# ManitoBoardLP1.net
KiCad netlist of a schematic drawn in EAGLE
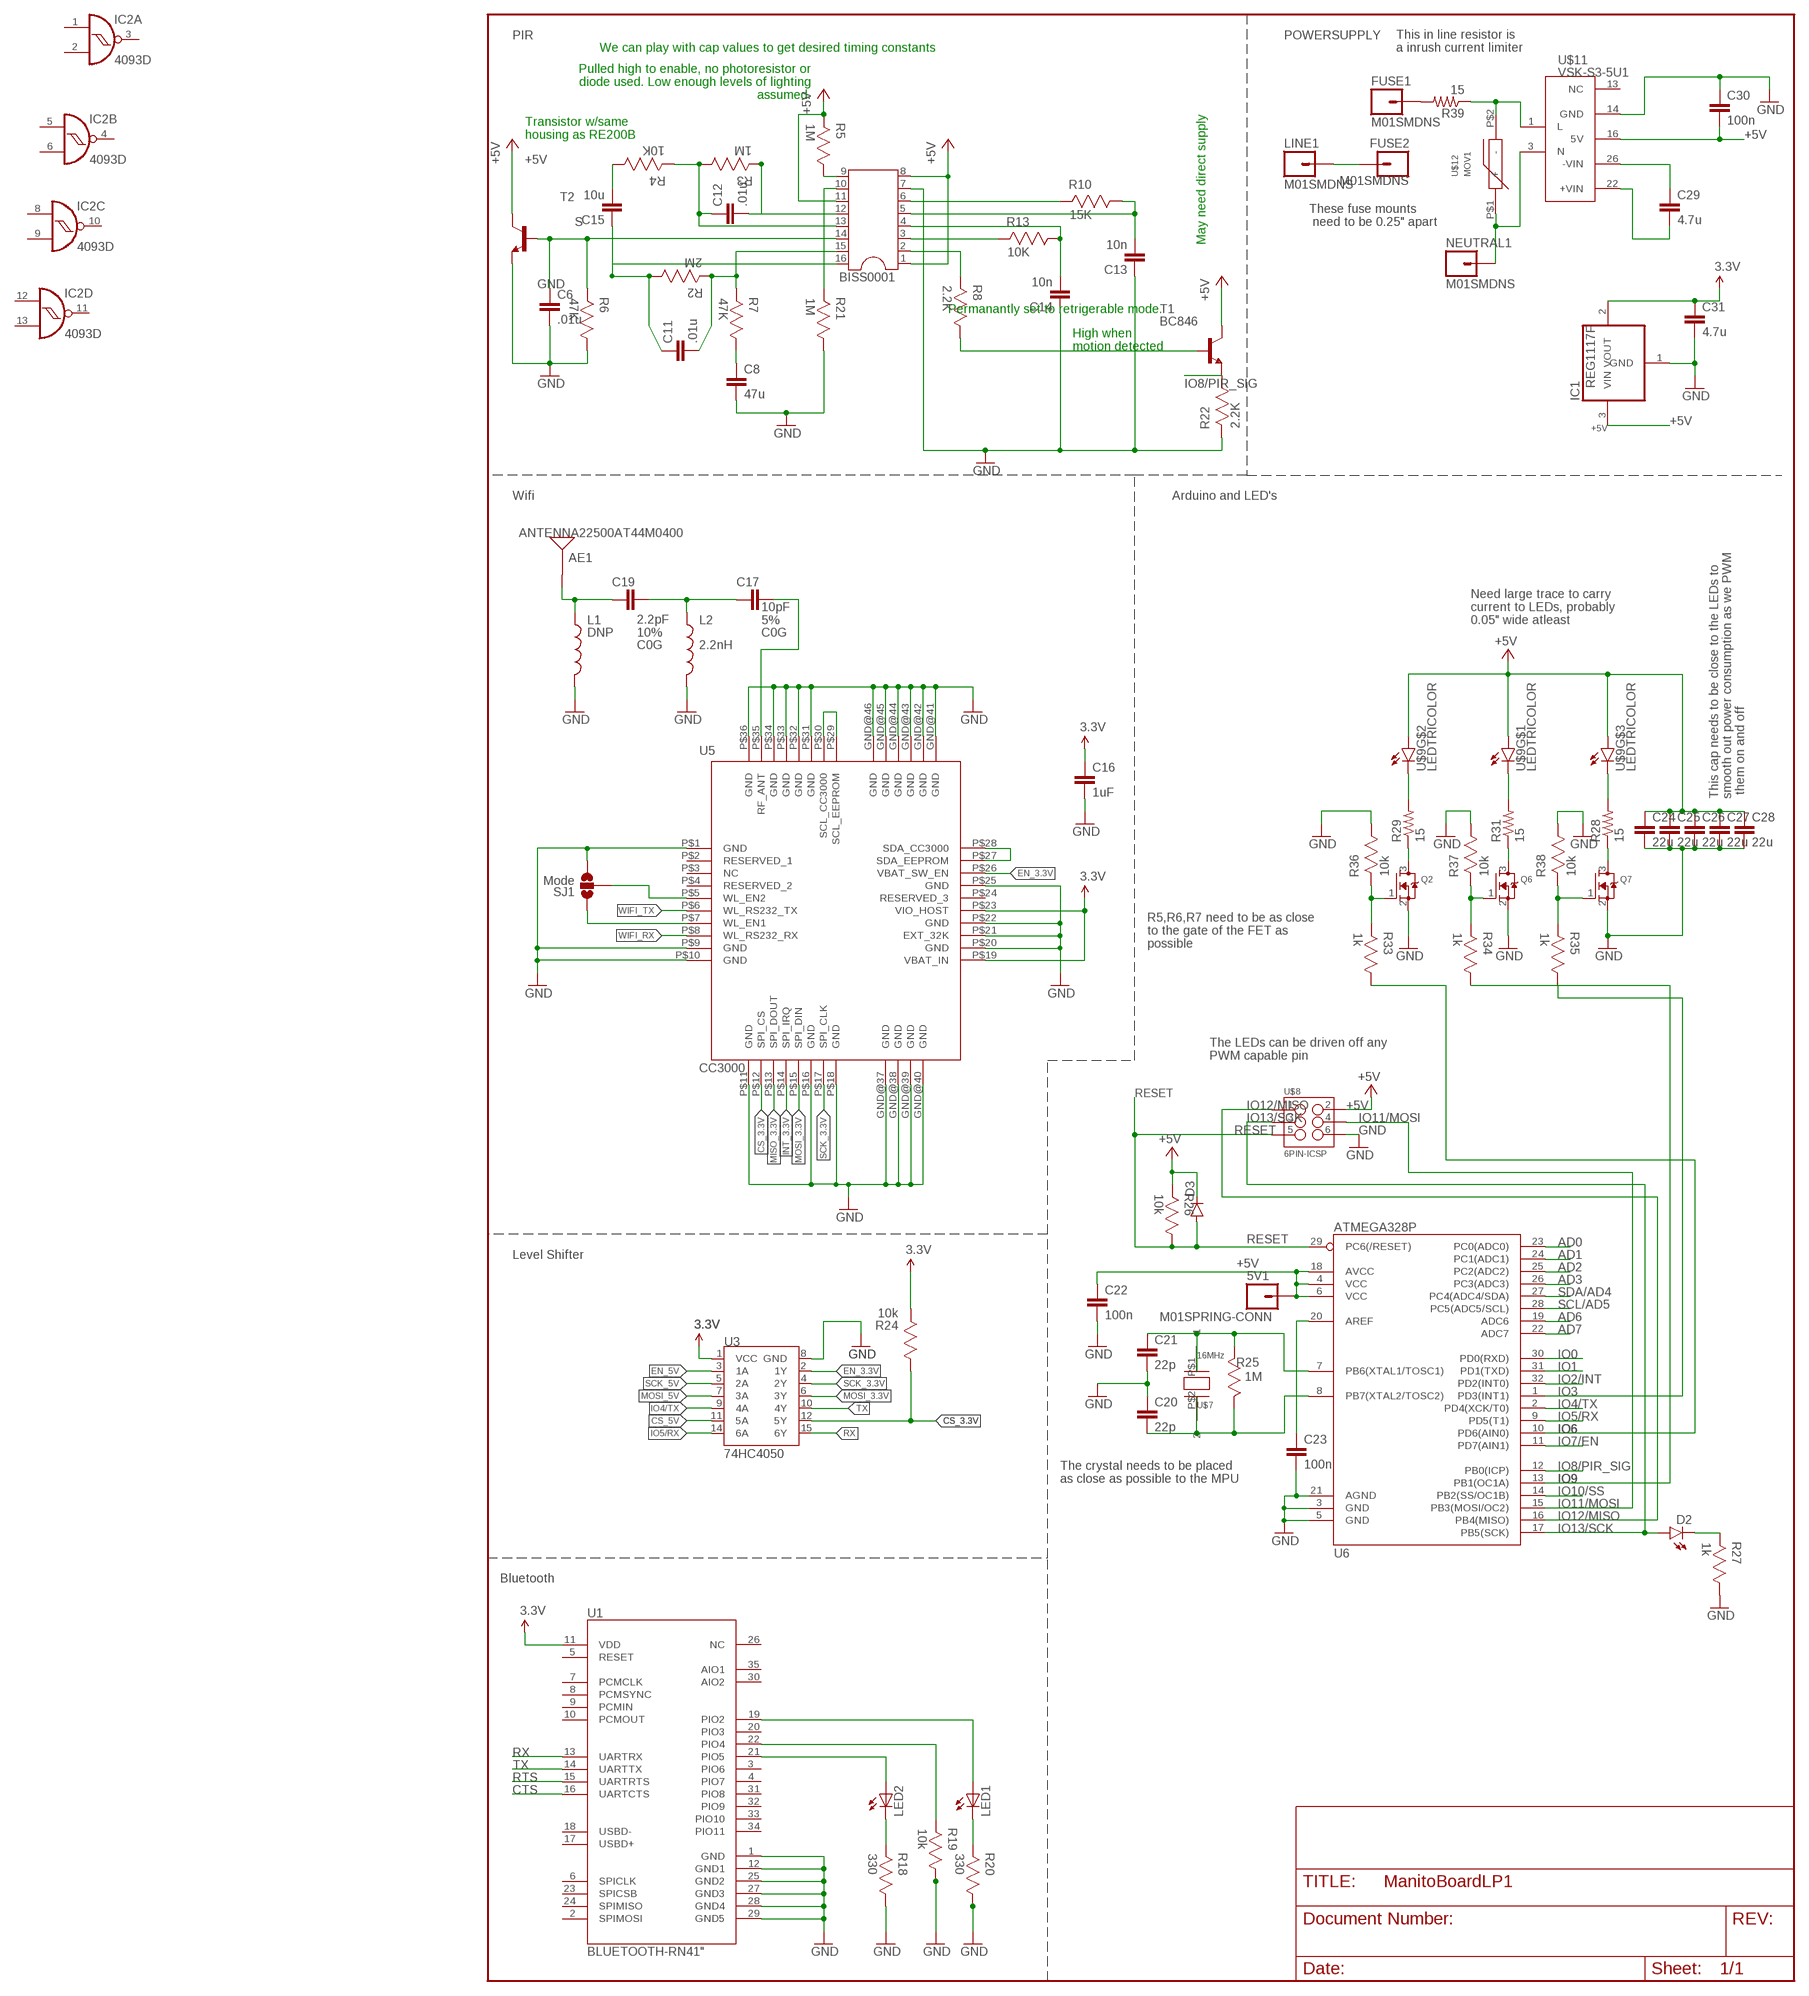
[diagram p0: schematic, sheet 1]

(export (version "E")
  (design (tool "Eeschema 10.0.6"))
  (components
    (comp (ref "5V1")
      (value "M01SPRING-CONN")
      (footprint "eagle-import:SPRING-CONNECTOR")
      (libsource (lib "eagle-import") (part "M01SPRING-CONN"))
    )
    (comp (ref "AE1")
      (value "ANTENNA22500AT44M0400")
      (footprint "eagle-import:ANTENNA-CHIP_2500AT44M0400")
      (libsource (lib "eagle-import") (part "ANTENNA22500AT44M0400"))
    )
    (comp (ref "BISS0001")
      (value "DIL16S")
      (footprint "eagle-import:SOCKET-16")
      (libsource (lib "eagle-import") (part "DIL16S"))
    )
    (comp (ref "C6")
      (value ".01u")
      (footprint "eagle-import:0805")
      (libsource (lib "eagle-import") (part "CAP0805"))
    )
    (comp (ref "C8")
      (value "47u")
      (footprint "eagle-import:0805")
      (libsource (lib "eagle-import") (part "CAP0805"))
    )
    (comp (ref "C11")
      (value ".01u")
      (footprint "eagle-import:0805")
      (libsource (lib "eagle-import") (part "CAP0805"))
    )
    (comp (ref "C12")
      (value ".01u")
      (footprint "eagle-import:0805")
      (libsource (lib "eagle-import") (part "CAP0805"))
    )
    (comp (ref "C13")
      (value "10n")
      (footprint "eagle-import:0805")
      (libsource (lib "eagle-import") (part "CAP0805"))
    )
    (comp (ref "C14")
      (value "10n")
      (footprint "eagle-import:0805")
      (libsource (lib "eagle-import") (part "CAP0805"))
    )
    (comp (ref "C15")
      (value "10u")
      (footprint "eagle-import:0805")
      (libsource (lib "eagle-import") (part "CAP0805"))
    )
    (comp (ref "C16")
      (value "1uF")
      (footprint "eagle-import:0805")
      (libsource (lib "eagle-import") (part "SparkFun-Capacitors_CAP0805"))
    )
    (comp (ref "C17")
      (value "10pF")
      (footprint "eagle-import:0603-CAP")
      (fields (field (name "COEFF") "C0G") (field (name "TOL") "5%"))
      (libsource (lib "eagle-import") (part "SparkFun-Capacitors_CAP0603-CAP"))
    )
    (comp (ref "C19")
      (value "2.2pF")
      (footprint "eagle-import:0603-CAP")
      (fields (field (name "COEFF") "C0G") (field (name "TOL") "10%"))
      (libsource (lib "eagle-import") (part "SparkFun-Capacitors_CAP0603-CAP"))
    )
    (comp (ref "C20")
      (value "22p")
      (footprint "eagle-import:0603-CAP")
      (libsource (lib "eagle-import") (part "CAP0603-CAP"))
    )
    (comp (ref "C21")
      (value "22p")
      (footprint "eagle-import:0603-CAP")
      (libsource (lib "eagle-import") (part "CAP0603-CAP"))
    )
    (comp (ref "C22")
      (value "100n")
      (footprint "eagle-import:0603-CAP")
      (libsource (lib "eagle-import") (part "CAP0603-CAP"))
    )
    (comp (ref "C23")
      (value "100n")
      (footprint "eagle-import:0603-CAP")
      (libsource (lib "eagle-import") (part "CAP0603-CAP"))
    )
    (comp (ref "C24")
      (value "22u")
      (footprint "eagle-import:0603-CAP")
      (libsource (lib "eagle-import") (part "CAP0603-CAP"))
    )
    (comp (ref "C25")
      (value "22u")
      (footprint "eagle-import:0603-CAP")
      (libsource (lib "eagle-import") (part "CAP0603-CAP"))
    )
    (comp (ref "C26")
      (value "22u")
      (footprint "eagle-import:0603-CAP")
      (libsource (lib "eagle-import") (part "CAP0603-CAP"))
    )
    (comp (ref "C27")
      (value "22u")
      (footprint "eagle-import:0603-CAP")
      (libsource (lib "eagle-import") (part "CAP0603-CAP"))
    )
    (comp (ref "C28")
      (value "22u")
      (footprint "eagle-import:0603-CAP")
      (libsource (lib "eagle-import") (part "CAP0603-CAP"))
    )
    (comp (ref "C29")
      (value "4.7u")
      (footprint "eagle-import:0603-CAP")
      (libsource (lib "eagle-import") (part "CAP0603-CAP"))
    )
    (comp (ref "C30")
      (value "100n")
      (footprint "eagle-import:0603-CAP")
      (libsource (lib "eagle-import") (part "CAP0603-CAP"))
    )
    (comp (ref "C31")
      (value "4.7u")
      (footprint "eagle-import:0603-CAP")
      (libsource (lib "eagle-import") (part "CAP0603-CAP"))
    )
    (comp (ref "D2")
      (value "LED-YELLOW0603")
      (footprint "eagle-import:LED-0603")
      (libsource (lib "eagle-import") (part "LED-YELLOW0603"))
    )
    (comp (ref "D3")
      (value "DIODE1N4148")
      (footprint "eagle-import:DIODE-1N4148")
      (libsource (lib "eagle-import") (part "DIODE1N4148"))
    )
    (comp (ref "FUSE1")
      (value "M01SMDNS")
      (footprint "eagle-import:1X01NS")
      (libsource (lib "eagle-import") (part "M01SMDNS"))
    )
    (comp (ref "FUSE2")
      (value "M01SMDNS")
      (footprint "eagle-import:1X01NS")
      (libsource (lib "eagle-import") (part "M01SMDNS"))
    )
    (comp (ref "IC1")
      (value "REG1117F")
      (footprint "eagle-import:DD-3")
      (fields (field (name "MF") "TEXAS INSTRUMENTS") (field (name "MPN") "REG1117FAKTTT"))
      (libsource (lib "eagle-import") (part "REG1117F"))
    )
    (comp (ref "IC2")
      (value "4093D")
      (footprint "eagle-import:SO14")
      (libsource (lib "eagle-import") (part "4093D"))
    )
    (comp (ref "L1")
      (value "DNP")
      (footprint "eagle-import:0603")
      (libsource (lib "eagle-import") (part "INDUCTOR0603"))
    )
    (comp (ref "L2")
      (value "2.2nH")
      (footprint "eagle-import:0603")
      (libsource (lib "eagle-import") (part "INDUCTOR0603"))
    )
    (comp (ref "LED1")
      (value "LED_ESML0603")
      (footprint "eagle-import:LED_SML0603")
      (libsource (lib "eagle-import") (part "LED_ESML0603"))
    )
    (comp (ref "LED2")
      (value "LED_ESML0603")
      (footprint "eagle-import:LED_SML0603")
      (libsource (lib "eagle-import") (part "LED_ESML0603"))
    )
    (comp (ref "LINE1")
      (value "M01SMDNS")
      (footprint "eagle-import:1X01NS")
      (libsource (lib "eagle-import") (part "M01SMDNS"))
    )
    (comp (ref "NEUTRAL1")
      (value "M01SMDNS")
      (footprint "eagle-import:1X01NS")
      (libsource (lib "eagle-import") (part "M01SMDNS"))
    )
    (comp (ref "Q2")
      (value "MOSFET-NREFLOW")
      (footprint "eagle-import:SOT23")
      (libsource (lib "eagle-import") (part "MOSFET-NREFLOW"))
    )
    (comp (ref "Q6")
      (value "MOSFET-NREFLOW")
      (footprint "eagle-import:SOT23")
      (libsource (lib "eagle-import") (part "MOSFET-NREFLOW"))
    )
    (comp (ref "Q7")
      (value "MOSFET-NREFLOW")
      (footprint "eagle-import:SOT23")
      (libsource (lib "eagle-import") (part "MOSFET-NREFLOW"))
    )
    (comp (ref "R2")
      (value "2M")
      (footprint "eagle-import:0603RESISTOR")
      (fields (field (name "MPN") "CRCW06031K21FKEA") (field (name "TOLERANCE") "± 1.0 %"))
      (libsource (lib "eagle-import") (part "0603RESISTOR1"))
    )
    (comp (ref "R3")
      (value "1M")
      (footprint "eagle-import:0603RESISTOR")
      (fields (field (name "MPN") "CRCW06031K21FKEA") (field (name "TOLERANCE") "± 1.0 %"))
      (libsource (lib "eagle-import") (part "0603RESISTOR1"))
    )
    (comp (ref "R4")
      (value "10K")
      (footprint "eagle-import:0603RESISTOR")
      (fields (field (name "MPN") "CRCW06031K21FKEA") (field (name "TOLERANCE") "± 1.0 %"))
      (libsource (lib "eagle-import") (part "0603RESISTOR1"))
    )
    (comp (ref "R5")
      (value "1M")
      (footprint "eagle-import:0603RESISTOR")
      (fields (field (name "MPN") "CRCW06031K21FKEA") (field (name "TOLERANCE") "± 1.0 %"))
      (libsource (lib "eagle-import") (part "0603RESISTOR1"))
    )
    (comp (ref "R6")
      (value "47K")
      (footprint "eagle-import:0603RESISTOR")
      (fields (field (name "MPN") "CRCW06031K21FKEA") (field (name "TOLERANCE") "± 1.0 %"))
      (libsource (lib "eagle-import") (part "0603RESISTOR1"))
    )
    (comp (ref "R7")
      (value "47K")
      (footprint "eagle-import:0603RESISTOR")
      (fields (field (name "MPN") "CRCW06031K21FKEA") (field (name "TOLERANCE") "± 1.0 %"))
      (libsource (lib "eagle-import") (part "0603RESISTOR1"))
    )
    (comp (ref "R8")
      (value "2.2K")
      (footprint "eagle-import:0603RESISTOR")
      (fields (field (name "MPN") "CRCW06031K21FKEA") (field (name "TOLERANCE") "± 1.0 %"))
      (libsource (lib "eagle-import") (part "0603RESISTOR1"))
    )
    (comp (ref "R10")
      (value "15K")
      (footprint "eagle-import:0603RESISTOR")
      (fields (field (name "MPN") "CRCW06031K21FKEA") (field (name "TOLERANCE") "± 1.0 %"))
      (libsource (lib "eagle-import") (part "0603RESISTOR1"))
    )
    (comp (ref "R13")
      (value "10K")
      (footprint "eagle-import:0603RESISTOR")
      (fields (field (name "MPN") "CRCW06031K21FKEA") (field (name "TOLERANCE") "± 1.0 %"))
      (libsource (lib "eagle-import") (part "0603RESISTOR1"))
    )
    (comp (ref "R18")
      (value "330")
      (footprint "eagle-import:0603RESISTOR")
      (fields (field (name "MPN") "CRCW06031K21FKEA") (field (name "TOLERANCE") "± 1.0 %"))
      (libsource (lib "eagle-import") (part "0603RESISTOR1"))
    )
    (comp (ref "R19")
      (value "10k")
      (footprint "eagle-import:0603RESISTOR")
      (fields (field (name "MPN") "CRCW06031K21FKEA") (field (name "TOLERANCE") "± 1.0 %"))
      (libsource (lib "eagle-import") (part "0603RESISTOR1"))
    )
    (comp (ref "R20")
      (value "330")
      (footprint "eagle-import:0603RESISTOR")
      (fields (field (name "MPN") "CRCW06031K21FKEA") (field (name "TOLERANCE") "± 1.0 %"))
      (libsource (lib "eagle-import") (part "0603RESISTOR1"))
    )
    (comp (ref "R21")
      (value "1M")
      (footprint "eagle-import:0603RESISTOR")
      (fields (field (name "MPN") "CRCW06031K21FKEA") (field (name "TOLERANCE") "± 1.0 %"))
      (libsource (lib "eagle-import") (part "0603RESISTOR1"))
    )
    (comp (ref "R22")
      (value "2.2K")
      (footprint "eagle-import:0603RESISTOR")
      (fields (field (name "MPN") "CRCW06031K21FKEA") (field (name "TOLERANCE") "± 1.0 %"))
      (libsource (lib "eagle-import") (part "0603RESISTOR1"))
    )
    (comp (ref "R24")
      (value "10k")
      (footprint "eagle-import:0603RESISTOR")
      (fields (field (name "MPN") "CRCW06031K21FKEA") (field (name "TOLERANCE") "± 1.0 %"))
      (libsource (lib "eagle-import") (part "0603RESISTOR1"))
    )
    (comp (ref "R25")
      (value "1M")
      (footprint "eagle-import:0603RESISTOR")
      (fields (field (name "MPN") "CRCW06031K21FKEA") (field (name "TOLERANCE") "± 1.0 %"))
      (libsource (lib "eagle-import") (part "0603RESISTOR1"))
    )
    (comp (ref "R26")
      (value "10k")
      (footprint "eagle-import:0603RESISTOR")
      (fields (field (name "MPN") "CRCW06031K21FKEA") (field (name "TOLERANCE") "± 1.0 %"))
      (libsource (lib "eagle-import") (part "0603RESISTOR1"))
    )
    (comp (ref "R27")
      (value "1k")
      (footprint "eagle-import:0603RESISTOR")
      (fields (field (name "MPN") "CRCW06031K21FKEA") (field (name "TOLERANCE") "± 1.0 %"))
      (libsource (lib "eagle-import") (part "0603RESISTOR1"))
    )
    (comp (ref "R28")
      (value "15")
      (footprint "eagle-import:AXIAL-0.6")
      (libsource (lib "eagle-import") (part "RESISTORPTH-1W"))
    )
    (comp (ref "R29")
      (value "15")
      (footprint "eagle-import:AXIAL-0.6")
      (libsource (lib "eagle-import") (part "RESISTORPTH-1W"))
    )
    (comp (ref "R31")
      (value "15")
      (footprint "eagle-import:AXIAL-0.6")
      (libsource (lib "eagle-import") (part "RESISTORPTH-1W"))
    )
    (comp (ref "R33")
      (value "1k")
      (footprint "eagle-import:0603RESISTOR")
      (fields (field (name "MPN") "CRCW06031K21FKEA") (field (name "TOLERANCE") "± 1.0 %"))
      (libsource (lib "eagle-import") (part "0603RESISTOR1"))
    )
    (comp (ref "R34")
      (value "1k")
      (footprint "eagle-import:0603RESISTOR")
      (fields (field (name "MPN") "CRCW06031K21FKEA") (field (name "TOLERANCE") "± 1.0 %"))
      (libsource (lib "eagle-import") (part "0603RESISTOR1"))
    )
    (comp (ref "R35")
      (value "1k")
      (footprint "eagle-import:0603RESISTOR")
      (fields (field (name "MPN") "CRCW06031K21FKEA") (field (name "TOLERANCE") "± 1.0 %"))
      (libsource (lib "eagle-import") (part "0603RESISTOR1"))
    )
    (comp (ref "R36")
      (value "10k")
      (footprint "eagle-import:0603RESISTOR")
      (fields (field (name "MPN") "CRCW06031K21FKEA") (field (name "TOLERANCE") "± 1.0 %"))
      (libsource (lib "eagle-import") (part "0603RESISTOR1"))
    )
    (comp (ref "R37")
      (value "10k")
      (footprint "eagle-import:0603RESISTOR")
      (fields (field (name "MPN") "CRCW06031K21FKEA") (field (name "TOLERANCE") "± 1.0 %"))
      (libsource (lib "eagle-import") (part "0603RESISTOR1"))
    )
    (comp (ref "R38")
      (value "10k")
      (footprint "eagle-import:0603RESISTOR")
      (fields (field (name "MPN") "CRCW06031K21FKEA") (field (name "TOLERANCE") "± 1.0 %"))
      (libsource (lib "eagle-import") (part "0603RESISTOR1"))
    )
    (comp (ref "R39")
      (value "15")
      (footprint "eagle-import:AXIAL-0.6")
      (libsource (lib "eagle-import") (part "RESISTORPTH-1W"))
    )
    (comp (ref "SJ1")
      (value "Mode")
      (footprint "eagle-import:SJ_3_PASTE1&2")
      (libsource (lib "eagle-import") (part "SOLDERJUMPER_2WAYPASTE1&2"))
    )
    (comp (ref "T1")
      (value "BC846")
      (footprint "eagle-import:SOT23")
      (libsource (lib "eagle-import") (part "BC846"))
    )
    (comp (ref "T2")
      (value "-NPN-TO5")
      (footprint "eagle-import:TO5")
      (libsource (lib "eagle-import") (part "-NPN-TO5"))
    )
    (comp (ref "U$7")
      (value "16MHz")
      (footprint "eagle-import:SMDCRYSTAL")
      (libsource (lib "eagle-import") (part "SMDCRYSTAL"))
    )
    (comp (ref "U$8")
      (value "6PIN-ICSP")
      (footprint "eagle-import:2X3-ICSP")
      (libsource (lib "eagle-import") (part "6PIN-ICSP"))
    )
    (comp (ref "U$9")
      (value "LEDTRICOLOR")
      (footprint "eagle-import:TRICOLORLED")
      (libsource (lib "eagle-import") (part "LEDTRICOLOR"))
    )
    (comp (ref "U$11")
      (value "VSK-S3-5U1")
      (footprint "eagle-import:VSK-S3-DCAC")
      (libsource (lib "eagle-import") (part "VSK-S3-5U1"))
    )
    (comp (ref "U$12")
      (value "MOV1")
      (footprint "eagle-import:MOV")
      (libsource (lib "eagle-import") (part "MOV1"))
    )
    (comp (ref "U1")
      (value "BLUETOOTH-RN41\"")
      (footprint "eagle-import:RN41")
      (libsource (lib "eagle-import") (part "BLUETOOTH-RN41{dblquote}"))
    )
    (comp (ref "U3")
      (value "74HC4050")
      (footprint "eagle-import:SO016")
      (libsource (lib "eagle-import") (part "HEX_CONVERTER"))
    )
    (comp (ref "U5")
      (value "CC3000")
      (footprint "eagle-import:QFN-46_CC3000")
      (libsource (lib "eagle-import") (part "CC3000"))
    )
    (comp (ref "U6")
      (value "ATMEGA328P")
      (footprint "eagle-import:TQFP32-08")
      (libsource (lib "eagle-import") (part "ATMEGA328_SMT"))
    )
  )
  (nets
    (net (code "1") (name "+5V") (class "Default")
      (node (ref "5V1") (pin "P$2") (pinfunction "1_P$2") (pintype "passive"))
      (node (ref "BISS0001") (pin "1") (pinfunction "1_1") (pintype "passive"))
      (node (ref "BISS0001") (pin "11") (pinfunction "11_11") (pintype "passive"))
      (node (ref "BISS0001") (pin "8") (pinfunction "8_8") (pintype "passive"))
      (node (ref "C22") (pin "1") (pinfunction "1_1") (pintype "passive"))
      (node (ref "C24") (pin "1") (pinfunction "1_1") (pintype "passive"))
      (node (ref "C25") (pin "1") (pinfunction "1_1") (pintype "passive"))
      (node (ref "C26") (pin "1") (pinfunction "1_1") (pintype "passive"))
      (node (ref "C27") (pin "1") (pinfunction "1_1") (pintype "passive"))
      (node (ref "C28") (pin "1") (pinfunction "1_1") (pintype "passive"))
      (node (ref "C30") (pin "2") (pinfunction "2_2") (pintype "passive"))
      (node (ref "D3") (pin "C") (pinfunction "C_C") (pintype "passive"))
      (node (ref "IC1") (pin "3") (pinfunction "VIN_3") (pintype "input"))
      (node (ref "R26") (pin "2") (pinfunction "2_2") (pintype "passive"))
      (node (ref "R5") (pin "2") (pinfunction "2_2") (pintype "passive"))
      (node (ref "T1") (pin "3") (pinfunction "C_3") (pintype "passive"))
      (node (ref "T2") (pin "3") (pinfunction "C_3") (pintype "passive"))
      (node (ref "U$11") (pin "16") (pinfunction "5V_16") (pintype "bidirectional"))
      (node (ref "U$8") (pin "2") (pinfunction "+5V_2") (pintype "power_in"))
      (node (ref "U$9") (pin "A1") (pinfunction "A_A1") (pintype "passive"))
      (node (ref "U$9") (pin "A2") (pinfunction "A_A2") (pintype "passive"))
      (node (ref "U$9") (pin "A3") (pinfunction "A_A3") (pintype "passive"))
      (node (ref "U6") (pin "18") (pinfunction "AVCC_18") (pintype "bidirectional"))
      (node (ref "U6") (pin "4") (pinfunction "VCC_4") (pintype "bidirectional"))
      (node (ref "U6") (pin "6") (pinfunction "VCC_6") (pintype "bidirectional"))
    )
    (net (code "2") (name "/AD0") (class "Default")
      (node (ref "U6") (pin "23") (pinfunction "PC0(ADC0)_23") (pintype "bidirectional"))
    )
    (net (code "3") (name "/AD1") (class "Default")
      (node (ref "U6") (pin "24") (pinfunction "PC1(ADC1)_24") (pintype "bidirectional"))
    )
    (net (code "4") (name "/AD2") (class "Default")
      (node (ref "U6") (pin "25") (pinfunction "PC2(ADC2)_25") (pintype "bidirectional"))
    )
    (net (code "5") (name "/AD3") (class "Default")
      (node (ref "U6") (pin "26") (pinfunction "PC3(ADC3)_26") (pintype "bidirectional"))
    )
    (net (code "6") (name "/AD6") (class "Default")
      (node (ref "U6") (pin "19") (pinfunction "ADC6_19") (pintype "bidirectional"))
    )
    (net (code "7") (name "/AD7") (class "Default")
      (node (ref "U6") (pin "22") (pinfunction "ADC7_22") (pintype "bidirectional"))
    )
    (net (code "8") (name "/CTS") (class "Default")
      (node (ref "U1") (pin "16") (pinfunction "UARTCTS_16") (pintype "bidirectional"))
    )
    (net (code "9") (name "/IO0") (class "Default")
      (node (ref "U6") (pin "30") (pinfunction "PD0(RXD)_30") (pintype "bidirectional"))
    )
    (net (code "10") (name "/IO1") (class "Default")
      (node (ref "U6") (pin "31") (pinfunction "PD1(TXD)_31") (pintype "bidirectional"))
    )
    (net (code "11") (name "/IO2{slash}INT") (class "Default")
      (node (ref "U6") (pin "32") (pinfunction "PD2(INT0)_32") (pintype "bidirectional"))
    )
    (net (code "12") (name "/IO3") (class "Default")
      (node (ref "R35") (pin "1") (pinfunction "1_1") (pintype "passive"))
      (node (ref "U6") (pin "1") (pinfunction "PD3(INT1)_1") (pintype "bidirectional"))
    )
    (net (code "13") (name "/IO6") (class "Default")
      (node (ref "R33") (pin "1") (pinfunction "1_1") (pintype "passive"))
      (node (ref "U6") (pin "10") (pinfunction "PD6(AIN0)_10") (pintype "bidirectional"))
    )
    (net (code "14") (name "/IO7{slash}EN") (class "Default")
      (node (ref "U6") (pin "11") (pinfunction "PD7(AIN1)_11") (pintype "bidirectional"))
    )
    (net (code "15") (name "/IO8{slash}PIR_SIG") (class "Default")
      (node (ref "R22") (pin "1") (pinfunction "1_1") (pintype "passive"))
      (node (ref "T1") (pin "2") (pinfunction "E_2") (pintype "passive"))
      (node (ref "U6") (pin "12") (pinfunction "PB0(ICP)_12") (pintype "bidirectional"))
    )
    (net (code "16") (name "/IO9") (class "Default")
      (node (ref "R34") (pin "1") (pinfunction "1_1") (pintype "passive"))
      (node (ref "U6") (pin "13") (pinfunction "PB1(OC1A)_13") (pintype "bidirectional"))
    )
    (net (code "17") (name "/IO10{slash}SS") (class "Default")
      (node (ref "U6") (pin "14") (pinfunction "PB2(SS/OC1B)_14") (pintype "bidirectional"))
    )
    (net (code "18") (name "/IO11{slash}MOSI") (class "Default")
      (node (ref "U$8") (pin "4") (pinfunction "MOSI_4") (pintype "bidirectional"))
      (node (ref "U6") (pin "15") (pinfunction "PB3(MOSI/OC2)_15") (pintype "bidirectional"))
    )
    (net (code "19") (name "/IO12{slash}MISO") (class "Default")
      (node (ref "U$8") (pin "1") (pinfunction "MISO_1") (pintype "bidirectional"))
      (node (ref "U6") (pin "16") (pinfunction "PB4(MISO)_16") (pintype "bidirectional"))
    )
    (net (code "20") (name "/IO13{slash}SCK") (class "Default")
      (node (ref "D2") (pin "A") (pinfunction "A_A") (pintype "passive"))
      (node (ref "U$8") (pin "3") (pinfunction "SCK_3") (pintype "bidirectional"))
      (node (ref "U6") (pin "17") (pinfunction "PB5(SCK)_17") (pintype "bidirectional"))
    )
    (net (code "22") (name "/RESET") (class "Default")
      (node (ref "D3") (pin "A") (pinfunction "A_A") (pintype "passive"))
      (node (ref "R26") (pin "1") (pinfunction "1_1") (pintype "passive"))
      (node (ref "U$8") (pin "5") (pinfunction "RESET_5") (pintype "bidirectional"))
      (node (ref "U6") (pin "29") (pinfunction "PC6(/RESET)_29") (pintype "bidirectional"))
    )
    (net (code "23") (name "/RTS") (class "Default")
      (node (ref "U1") (pin "15") (pinfunction "UARTRTS_15") (pintype "bidirectional"))
    )
    (net (code "24") (name "/S") (class "Default")
      (node (ref "BISS0001") (pin "14") (pinfunction "14_14") (pintype "passive"))
      (node (ref "C6") (pin "1") (pinfunction "1_1") (pintype "passive"))
      (node (ref "R6") (pin "2") (pinfunction "2_2") (pintype "passive"))
      (node (ref "T2") (pin "2") (pinfunction "B_2") (pintype "passive"))
    )
    (net (code "25") (name "/SCL{slash}AD5") (class "Default")
      (node (ref "U6") (pin "28") (pinfunction "PC5(ADC5/SCL)_28") (pintype "bidirectional"))
    )
    (net (code "26") (name "/SDA{slash}AD4") (class "Default")
      (node (ref "U6") (pin "27") (pinfunction "PC4(ADC4/SDA)_27") (pintype "bidirectional"))
    )
    (net (code "27") (name "3.3V") (class "Default")
      (node (ref "C16") (pin "1") (pinfunction "1_1") (pintype "passive"))
      (node (ref "C31") (pin "1") (pinfunction "1_1") (pintype "passive"))
      (node (ref "IC1") (pin "2") (pinfunction "VOUT_2") (pintype "output"))
      (node (ref "R24") (pin "2") (pinfunction "2_2") (pintype "passive"))
      (node (ref "U1") (pin "11") (pinfunction "VDD_11") (pintype "bidirectional"))
      (node (ref "U3") (pin "1") (pinfunction "VCC_1") (pintype "bidirectional"))
      (node (ref "U5") (pin "P$19") (pinfunction "VBAT_IN_P$19") (pintype "bidirectional"))
      (node (ref "U5") (pin "P$23") (pinfunction "VIO_HOST_P$23") (pintype "bidirectional"))
    )
    (net (code "28") (name "CS_3.3V") (class "Default")
      (node (ref "R24") (pin "1") (pinfunction "1_1") (pintype "passive"))
      (node (ref "U3") (pin "12") (pinfunction "5Y_12") (pintype "bidirectional"))
      (node (ref "U5") (pin "P$12") (pinfunction "SPI_CS_P$12") (pintype "bidirectional"))
    )
    (net (code "29") (name "CS_5V") (class "Default")
      (node (ref "U3") (pin "11") (pinfunction "5A_11") (pintype "bidirectional"))
    )
    (net (code "30") (name "EN_3.3V") (class "Default")
      (node (ref "U3") (pin "2") (pinfunction "1Y_2") (pintype "bidirectional"))
      (node (ref "U5") (pin "P$26") (pinfunction "VBAT_SW_EN_P$26") (pintype "bidirectional"))
    )
    (net (code "31") (name "EN_5V") (class "Default")
      (node (ref "U3") (pin "3") (pinfunction "1A_3") (pintype "bidirectional"))
    )
    (net (code "32") (name "GND") (class "Default")
      (node (ref "BISS0001") (pin "7") (pinfunction "7_7") (pintype "passive"))
      (node (ref "C13") (pin "1") (pinfunction "1_1") (pintype "passive"))
      (node (ref "C14") (pin "1") (pinfunction "1_1") (pintype "passive"))
      (node (ref "C16") (pin "2") (pinfunction "2_2") (pintype "passive"))
      (node (ref "C20") (pin "1") (pinfunction "1_1") (pintype "passive"))
      (node (ref "C21") (pin "2") (pinfunction "2_2") (pintype "passive"))
      (node (ref "C22") (pin "2") (pinfunction "2_2") (pintype "passive"))
      (node (ref "C23") (pin "2") (pinfunction "2_2") (pintype "passive"))
      (node (ref "C24") (pin "2") (pinfunction "2_2") (pintype "passive"))
      (node (ref "C25") (pin "2") (pinfunction "2_2") (pintype "passive"))
      (node (ref "C26") (pin "2") (pinfunction "2_2") (pintype "passive"))
      (node (ref "C27") (pin "2") (pinfunction "2_2") (pintype "passive"))
      (node (ref "C28") (pin "2") (pinfunction "2_2") (pintype "passive"))
      (node (ref "C30") (pin "1") (pinfunction "1_1") (pintype "passive"))
      (node (ref "C31") (pin "2") (pinfunction "2_2") (pintype "passive"))
      (node (ref "C6") (pin "2") (pinfunction "2_2") (pintype "passive"))
      (node (ref "C8") (pin "2") (pinfunction "2_2") (pintype "passive"))
      (node (ref "IC1") (pin "1") (pinfunction "GND_1") (pintype "power_in"))
      (node (ref "L1") (pin "2") (pinfunction "2_2") (pintype "passive"))
      (node (ref "L2") (pin "2") (pinfunction "2_2") (pintype "passive"))
      (node (ref "Q2") (pin "2") (pinfunction "S_2") (pintype "bidirectional"))
      (node (ref "Q6") (pin "2") (pinfunction "S_2") (pintype "bidirectional"))
      (node (ref "Q7") (pin "2") (pinfunction "S_2") (pintype "bidirectional"))
      (node (ref "R18") (pin "1") (pinfunction "1_1") (pintype "passive"))
      (node (ref "R19") (pin "1") (pinfunction "1_1") (pintype "passive"))
      (node (ref "R20") (pin "1") (pinfunction "1_1") (pintype "passive"))
      (node (ref "R21") (pin "1") (pinfunction "1_1") (pintype "passive"))
      (node (ref "R22") (pin "2") (pinfunction "2_2") (pintype "passive"))
      (node (ref "R27") (pin "1") (pinfunction "1_1") (pintype "passive"))
      (node (ref "R36") (pin "1") (pinfunction "1_1") (pintype "passive"))
      (node (ref "R37") (pin "1") (pinfunction "1_1") (pintype "passive"))
      (node (ref "R38") (pin "1") (pinfunction "1_1") (pintype "passive"))
      (node (ref "R6") (pin "1") (pinfunction "1_1") (pintype "passive"))
      (node (ref "SJ1") (pin "3") (pinfunction "3_3") (pintype "passive"))
      (node (ref "T2") (pin "1") (pinfunction "E_1") (pintype "passive"))
      (node (ref "U$11") (pin "14") (pinfunction "GND_14") (pintype "bidirectional"))
      (node (ref "U$8") (pin "6") (pinfunction "GND_6") (pintype "power_in"))
      (node (ref "U1") (pin "1") (pinfunction "GND_1") (pintype "bidirectional"))
      (node (ref "U1") (pin "12") (pinfunction "GND1_12") (pintype "bidirectional"))
      (node (ref "U1") (pin "25") (pinfunction "GND2_25") (pintype "bidirectional"))
      (node (ref "U1") (pin "27") (pinfunction "GND3_27") (pintype "bidirectional"))
      (node (ref "U1") (pin "28") (pinfunction "GND4_28") (pintype "bidirectional"))
      (node (ref "U1") (pin "29") (pinfunction "GND5_29") (pintype "bidirectional"))
      (node (ref "U3") (pin "8") (pinfunction "GND_8") (pintype "bidirectional"))
      (node (ref "U5") (pin "GND@37") (pinfunction "GND_GND@37") (pintype "bidirectional"))
      (node (ref "U5") (pin "GND@38") (pinfunction "GND_GND@38") (pintype "bidirectional"))
      (node (ref "U5") (pin "GND@39") (pinfunction "GND_GND@39") (pintype "bidirectional"))
      (node (ref "U5") (pin "GND@40") (pinfunction "GND_GND@40") (pintype "bidirectional"))
      (node (ref "U5") (pin "GND@41") (pinfunction "GND_GND@41") (pintype "bidirectional"))
      (node (ref "U5") (pin "GND@42") (pinfunction "GND_GND@42") (pintype "bidirectional"))
      (node (ref "U5") (pin "GND@43") (pinfunction "GND_GND@43") (pintype "bidirectional"))
      (node (ref "U5") (pin "GND@44") (pinfunction "GND_GND@44") (pintype "bidirectional"))
      (node (ref "U5") (pin "GND@45") (pinfunction "GND_GND@45") (pintype "bidirectional"))
      (node (ref "U5") (pin "GND@46") (pinfunction "GND_GND@46") (pintype "bidirectional"))
      (node (ref "U5") (pin "P$1") (pinfunction "GND_P$1") (pintype "bidirectional"))
      (node (ref "U5") (pin "P$10") (pinfunction "GND_P$10") (pintype "bidirectional"))
      (node (ref "U5") (pin "P$11") (pinfunction "GND_P$11") (pintype "bidirectional"))
      (node (ref "U5") (pin "P$16") (pinfunction "GND_P$16") (pintype "bidirectional"))
      (node (ref "U5") (pin "P$18") (pinfunction "GND_P$18") (pintype "bidirectional"))
      (node (ref "U5") (pin "P$20") (pinfunction "GND_P$20") (pintype "bidirectional"))
      (node (ref "U5") (pin "P$21") (pinfunction "EXT_32K_P$21") (pintype "bidirectional"))
      (node (ref "U5") (pin "P$22") (pinfunction "GND_P$22") (pintype "bidirectional"))
      (node (ref "U5") (pin "P$25") (pinfunction "GND_P$25") (pintype "bidirectional"))
      (node (ref "U5") (pin "P$31") (pinfunction "GND_P$31") (pintype "bidirectional"))
      (node (ref "U5") (pin "P$32") (pinfunction "GND_P$32") (pintype "bidirectional"))
      (node (ref "U5") (pin "P$33") (pinfunction "GND_P$33") (pintype "bidirectional"))
      (node (ref "U5") (pin "P$34") (pinfunction "GND_P$34") (pintype "bidirectional"))
      (node (ref "U5") (pin "P$36") (pinfunction "GND_P$36") (pintype "bidirectional"))
      (node (ref "U5") (pin "P$9") (pinfunction "GND_P$9") (pintype "bidirectional"))
      (node (ref "U6") (pin "21") (pinfunction "AGND_21") (pintype "bidirectional"))
      (node (ref "U6") (pin "3") (pinfunction "GND_3") (pintype "bidirectional"))
      (node (ref "U6") (pin "5") (pinfunction "GND_5") (pintype "bidirectional"))
    )
    (net (code "33") (name "INT_3.3V") (class "Default")
      (node (ref "U5") (pin "P$14") (pinfunction "SPI_IRQ_P$14") (pintype "bidirectional"))
    )
    (net (code "34") (name "IO4{slash}TX") (class "Default")
      (node (ref "U3") (pin "9") (pinfunction "4A_9") (pintype "bidirectional"))
      (node (ref "U6") (pin "2") (pinfunction "PD4(XCK/T0)_2") (pintype "bidirectional"))
    )
    (net (code "35") (name "IO5{slash}RX") (class "Default")
      (node (ref "U3") (pin "14") (pinfunction "6A_14") (pintype "bidirectional"))
      (node (ref "U6") (pin "9") (pinfunction "PD5(T1)_9") (pintype "bidirectional"))
    )
    (net (code "36") (name "MISO_3.3V") (class "Default")
      (node (ref "U5") (pin "P$13") (pinfunction "SPI_DOUT_P$13") (pintype "bidirectional"))
    )
    (net (code "37") (name "MOSI_3.3V") (class "Default")
      (node (ref "U3") (pin "6") (pinfunction "3Y_6") (pintype "bidirectional"))
      (node (ref "U5") (pin "P$15") (pinfunction "SPI_DIN_P$15") (pintype "bidirectional"))
    )
    (net (code "38") (name "MOSI_5V") (class "Default")
      (node (ref "U3") (pin "7") (pinfunction "3A_7") (pintype "bidirectional"))
    )
    (net (code "39") (name "Net-(AE1-SIGNAL)") (class "Default")
      (node (ref "AE1") (pin "FEED") (pinfunction "SIGNAL_FEED") (pintype "bidirectional"))
      (node (ref "C19") (pin "1") (pinfunction "1_1") (pintype "passive"))
      (node (ref "L1") (pin "1") (pinfunction "1_1") (pintype "passive"))
    )
    (net (code "40") (name "Net-(BISS0001-Pad2)") (class "Default")
      (node (ref "BISS0001") (pin "2") (pinfunction "2_2") (pintype "passive"))
      (node (ref "R8") (pin "2") (pinfunction "2_2") (pintype "passive"))
    )
    (net (code "41") (name "Net-(BISS0001-Pad3)") (class "Default")
      (node (ref "BISS0001") (pin "3") (pinfunction "3_3") (pintype "passive"))
      (node (ref "R13") (pin "2") (pinfunction "2_2") (pintype "passive"))
    )
    (net (code "42") (name "Net-(BISS0001-Pad4)") (class "Default")
      (node (ref "BISS0001") (pin "4") (pinfunction "4_4") (pintype "passive"))
      (node (ref "C14") (pin "2") (pinfunction "2_2") (pintype "passive"))
      (node (ref "R13") (pin "1") (pinfunction "1_1") (pintype "passive"))
    )
    (net (code "43") (name "Net-(BISS0001-Pad5)") (class "Default")
      (node (ref "BISS0001") (pin "5") (pinfunction "5_5") (pintype "passive"))
      (node (ref "C13") (pin "2") (pinfunction "2_2") (pintype "passive"))
      (node (ref "R10") (pin "1") (pinfunction "1_1") (pintype "passive"))
    )
    (net (code "44") (name "Net-(BISS0001-Pad6)") (class "Default")
      (node (ref "BISS0001") (pin "6") (pinfunction "6_6") (pintype "passive"))
      (node (ref "R10") (pin "2") (pinfunction "2_2") (pintype "passive"))
    )
    (net (code "45") (name "Net-(BISS0001-Pad9)") (class "Default")
      (node (ref "BISS0001") (pin "9") (pinfunction "9_9") (pintype "passive"))
      (node (ref "R5") (pin "1") (pinfunction "1_1") (pintype "passive"))
    )
    (net (code "46") (name "Net-(BISS0001-Pad10)") (class "Default")
      (node (ref "BISS0001") (pin "10") (pinfunction "10_10") (pintype "passive"))
      (node (ref "R21") (pin "2") (pinfunction "2_2") (pintype "passive"))
    )
    (net (code "47") (name "Net-(BISS0001-Pad12)") (class "Default")
      (node (ref "BISS0001") (pin "12") (pinfunction "12_12") (pintype "passive"))
      (node (ref "C12") (pin "2") (pinfunction "2_2") (pintype "passive"))
      (node (ref "R3") (pin "2") (pinfunction "2_2") (pintype "passive"))
    )
    (net (code "48") (name "Net-(BISS0001-Pad13)") (class "Default")
      (node (ref "BISS0001") (pin "13") (pinfunction "13_13") (pintype "passive"))
      (node (ref "C12") (pin "1") (pinfunction "1_1") (pintype "passive"))
      (node (ref "R3") (pin "1") (pinfunction "1_1") (pintype "passive"))
      (node (ref "R4") (pin "2") (pinfunction "2_2") (pintype "passive"))
    )
    (net (code "49") (name "Net-(BISS0001-Pad15)") (class "Default")
      (node (ref "BISS0001") (pin "15") (pinfunction "15_15") (pintype "passive"))
      (node (ref "C11") (pin "2") (pinfunction "2_2") (pintype "passive"))
      (node (ref "R2") (pin "2") (pinfunction "2_2") (pintype "passive"))
      (node (ref "R7") (pin "2") (pinfunction "2_2") (pintype "passive"))
    )
    (net (code "50") (name "Net-(BISS0001-Pad16)") (class "Default")
      (node (ref "BISS0001") (pin "16") (pinfunction "16_16") (pintype "passive"))
      (node (ref "C11") (pin "1") (pinfunction "1_1") (pintype "passive"))
      (node (ref "C15") (pin "1") (pinfunction "1_1") (pintype "passive"))
      (node (ref "R2") (pin "1") (pinfunction "1_1") (pintype "passive"))
    )
    (net (code "51") (name "Net-(C8-Pad1)") (class "Default")
      (node (ref "C8") (pin "1") (pinfunction "1_1") (pintype "passive"))
      (node (ref "R7") (pin "1") (pinfunction "1_1") (pintype "passive"))
    )
    (net (code "52") (name "Net-(C15-Pad2)") (class "Default")
      (node (ref "C15") (pin "2") (pinfunction "2_2") (pintype "passive"))
      (node (ref "R4") (pin "1") (pinfunction "1_1") (pintype "passive"))
    )
    (net (code "53") (name "Net-(C17-Pad1)") (class "Default")
      (node (ref "C17") (pin "1") (pinfunction "1_1") (pintype "passive"))
      (node (ref "C19") (pin "2") (pinfunction "2_2") (pintype "passive"))
      (node (ref "L2") (pin "1") (pinfunction "1_1") (pintype "passive"))
    )
    (net (code "54") (name "Net-(D2-PadC)") (class "Default")
      (node (ref "D2") (pin "C") (pinfunction "C_C") (pintype "passive"))
      (node (ref "R27") (pin "2") (pinfunction "2_2") (pintype "passive"))
    )
    (net (code "55") (name "Net-(FUSE2-Pad1)") (class "Default")
      (node (ref "FUSE2") (pin "1") (pinfunction "1_1") (pintype "passive"))
      (node (ref "LINE1") (pin "1") (pinfunction "1_1") (pintype "passive"))
    )
    (net (code "56") (name "Net-(LED1-PadC)") (class "Default")
      (node (ref "LED1") (pin "C") (pinfunction "C_C") (pintype "passive"))
      (node (ref "R20") (pin "2") (pinfunction "2_2") (pintype "passive"))
    )
    (net (code "57") (name "Net-(LED2-PadC)") (class "Default")
      (node (ref "LED2") (pin "C") (pinfunction "C_C") (pintype "passive"))
      (node (ref "R18") (pin "2") (pinfunction "2_2") (pintype "passive"))
    )
    (net (code "58") (name "Net-(Q2-D)") (class "Default")
      (node (ref "Q2") (pin "3") (pinfunction "D_3") (pintype "bidirectional"))
      (node (ref "R29") (pin "P$1") (pinfunction "1_P$1") (pintype "passive"))
    )
    (net (code "59") (name "Net-(Q2-G)") (class "Default")
      (node (ref "Q2") (pin "1") (pinfunction "G_1") (pintype "bidirectional"))
      (node (ref "R33") (pin "2") (pinfunction "2_2") (pintype "passive"))
      (node (ref "R36") (pin "2") (pinfunction "2_2") (pintype "passive"))
    )
    (net (code "60") (name "Net-(Q6-D)") (class "Default")
      (node (ref "Q6") (pin "3") (pinfunction "D_3") (pintype "bidirectional"))
      (node (ref "R31") (pin "P$1") (pinfunction "1_P$1") (pintype "passive"))
    )
    (net (code "61") (name "Net-(Q6-G)") (class "Default")
      (node (ref "Q6") (pin "1") (pinfunction "G_1") (pintype "bidirectional"))
      (node (ref "R34") (pin "2") (pinfunction "2_2") (pintype "passive"))
      (node (ref "R37") (pin "2") (pinfunction "2_2") (pintype "passive"))
    )
    (net (code "62") (name "Net-(Q7-D)") (class "Default")
      (node (ref "Q7") (pin "3") (pinfunction "D_3") (pintype "bidirectional"))
      (node (ref "R28") (pin "P$1") (pinfunction "1_P$1") (pintype "passive"))
    )
    (net (code "63") (name "Net-(Q7-G)") (class "Default")
      (node (ref "Q7") (pin "1") (pinfunction "G_1") (pintype "bidirectional"))
      (node (ref "R35") (pin "2") (pinfunction "2_2") (pintype "passive"))
      (node (ref "R38") (pin "2") (pinfunction "2_2") (pintype "passive"))
    )
    (net (code "64") (name "Net-(R28-2)") (class "Default")
      (node (ref "R28") (pin "P$2") (pinfunction "2_P$2") (pintype "passive"))
      (node (ref "U$9") (pin "C3") (pinfunction "C_C3") (pintype "passive"))
    )
    (net (code "65") (name "Net-(R29-2)") (class "Default")
      (node (ref "R29") (pin "P$2") (pinfunction "2_P$2") (pintype "passive"))
      (node (ref "U$9") (pin "C2") (pinfunction "C_C2") (pintype "passive"))
    )
    (net (code "66") (name "Net-(R31-2)") (class "Default")
      (node (ref "R31") (pin "P$2") (pinfunction "2_P$2") (pintype "passive"))
      (node (ref "U$9") (pin "C1") (pinfunction "C_C1") (pintype "passive"))
    )
    (net (code "67") (name "Net-(R39-1)") (class "Default")
      (node (ref "R39") (pin "P$1") (pinfunction "1_P$1") (pintype "passive"))
      (node (ref "U$11") (pin "1") (pinfunction "L_1") (pintype "bidirectional"))
      (node (ref "U$12") (pin "P$2") (pinfunction "-_P$2") (pintype "bidirectional"))
    )
    (net (code "68") (name "Net-(R39-2)") (class "Default")
      (node (ref "FUSE1") (pin "1") (pinfunction "1_1") (pintype "passive"))
      (node (ref "R39") (pin "P$2") (pinfunction "2_P$2") (pintype "passive"))
    )
    (net (code "69") (name "Net-(T1-B)") (class "Default")
      (node (ref "R8") (pin "1") (pinfunction "1_1") (pintype "passive"))
      (node (ref "T1") (pin "1") (pinfunction "B_1") (pintype "passive"))
    )
    (net (code "70") (name "Net-(U$7-1)") (class "Default")
      (node (ref "C21") (pin "1") (pinfunction "1_1") (pintype "passive"))
      (node (ref "R25") (pin "2") (pinfunction "2_2") (pintype "passive"))
      (node (ref "U$7") (pin "P$1") (pinfunction "1_P$1") (pintype "bidirectional"))
      (node (ref "U6") (pin "7") (pinfunction "PB6(XTAL1/TOSC1)_7") (pintype "bidirectional"))
    )
    (net (code "71") (name "Net-(U$7-2)") (class "Default")
      (node (ref "C20") (pin "2") (pinfunction "2_2") (pintype "passive"))
      (node (ref "R25") (pin "1") (pinfunction "1_1") (pintype "passive"))
      (node (ref "U$7") (pin "P$2") (pinfunction "2_P$2") (pintype "bidirectional"))
      (node (ref "U6") (pin "8") (pinfunction "PB7(XTAL2/TOSC2)_8") (pintype "bidirectional"))
    )
    (net (code "72") (name "Net-(U$11-+VIN)") (class "Default")
      (node (ref "C29") (pin "2") (pinfunction "2_2") (pintype "passive"))
      (node (ref "U$11") (pin "22") (pinfunction "+VIN_22") (pintype "bidirectional"))
    )
    (net (code "73") (name "Net-(U$11--VIN)") (class "Default")
      (node (ref "C29") (pin "1") (pinfunction "1_1") (pintype "passive"))
      (node (ref "U$11") (pin "26") (pinfunction "-VIN_26") (pintype "bidirectional"))
    )
    (net (code "74") (name "Net-(U$11-N)") (class "Default")
      (node (ref "NEUTRAL1") (pin "1") (pinfunction "1_1") (pintype "passive"))
      (node (ref "U$11") (pin "3") (pinfunction "N_3") (pintype "bidirectional"))
      (node (ref "U$12") (pin "P$1") (pinfunction "+_P$1") (pintype "bidirectional"))
    )
    (net (code "75") (name "Net-(U1-PIO2)") (class "Default")
      (node (ref "LED1") (pin "A") (pinfunction "A_A") (pintype "passive"))
      (node (ref "U1") (pin "19") (pinfunction "PIO2_19") (pintype "bidirectional"))
    )
    (net (code "76") (name "Net-(U1-PIO4)") (class "Default")
      (node (ref "R19") (pin "2") (pinfunction "2_2") (pintype "passive"))
      (node (ref "U1") (pin "22") (pinfunction "PIO4_22") (pintype "bidirectional"))
    )
    (net (code "77") (name "Net-(U1-PIO5)") (class "Default")
      (node (ref "LED2") (pin "A") (pinfunction "A_A") (pintype "passive"))
      (node (ref "U1") (pin "21") (pinfunction "PIO5_21") (pintype "bidirectional"))
    )
    (net (code "78") (name "Net-(U5-RF_ANT)") (class "Default")
      (node (ref "C17") (pin "2") (pinfunction "2_2") (pintype "passive"))
      (node (ref "U5") (pin "P$35") (pinfunction "RF_ANT_P$35") (pintype "bidirectional"))
    )
    (net (code "79") (name "Net-(U5-SCL_CC3000)") (class "Default")
      (node (ref "U5") (pin "P$29") (pinfunction "SCL_EEPROM_P$29") (pintype "bidirectional"))
      (node (ref "U5") (pin "P$30") (pinfunction "SCL_CC3000_P$30") (pintype "bidirectional"))
    )
    (net (code "80") (name "Net-(U5-SDA_CC3000)") (class "Default")
      (node (ref "U5") (pin "P$27") (pinfunction "SDA_EEPROM_P$27") (pintype "bidirectional"))
      (node (ref "U5") (pin "P$28") (pinfunction "SDA_CC3000_P$28") (pintype "bidirectional"))
    )
    (net (code "81") (name "Net-(U5-WL_EN1)") (class "Default")
      (node (ref "SJ1") (pin "1") (pinfunction "1_1") (pintype "passive"))
      (node (ref "U5") (pin "P$7") (pinfunction "WL_EN1_P$7") (pintype "bidirectional"))
    )
    (net (code "82") (name "Net-(U5-WL_EN2)") (class "Default")
      (node (ref "SJ1") (pin "2") (pinfunction "2_2") (pintype "passive"))
      (node (ref "U5") (pin "P$5") (pinfunction "WL_EN2_P$5") (pintype "bidirectional"))
    )
    (net (code "83") (name "Net-(U6-AREF)") (class "Default")
      (node (ref "C23") (pin "1") (pinfunction "1_1") (pintype "passive"))
      (node (ref "U6") (pin "20") (pinfunction "AREF_20") (pintype "bidirectional"))
    )
    (net (code "84") (name "RX") (class "Default")
      (node (ref "U1") (pin "13") (pinfunction "UARTRX_13") (pintype "bidirectional"))
      (node (ref "U3") (pin "15") (pinfunction "6Y_15") (pintype "bidirectional"))
    )
    (net (code "85") (name "SCK_3.3V") (class "Default")
      (node (ref "U3") (pin "4") (pinfunction "2Y_4") (pintype "bidirectional"))
      (node (ref "U5") (pin "P$17") (pinfunction "SPI_CLK_P$17") (pintype "bidirectional"))
    )
    (net (code "86") (name "SCK_5V") (class "Default")
      (node (ref "U3") (pin "5") (pinfunction "2A_5") (pintype "bidirectional"))
    )
    (net (code "87") (name "TX") (class "Default")
      (node (ref "U1") (pin "14") (pinfunction "UARTTX_14") (pintype "bidirectional"))
      (node (ref "U3") (pin "10") (pinfunction "4Y_10") (pintype "bidirectional"))
    )
    (net (code "88") (name "WIFI_RX") (class "Default")
      (node (ref "U5") (pin "P$8") (pinfunction "WL_RS232_RX_P$8") (pintype "bidirectional"))
    )
    (net (code "89") (name "WIFI_TX") (class "Default")
      (node (ref "U5") (pin "P$6") (pinfunction "WL_RS232_TX_P$6") (pintype "bidirectional"))
    )
    (net (code "90") (name "unconnected-(IC2A-I0-Pad1)") (class "Default")
      (node (ref "IC2") (pin "1") (pinfunction "I0_1") (pintype "input"))
    )
    (net (code "91") (name "unconnected-(IC2A-I1-Pad2)") (class "Default")
      (node (ref "IC2") (pin "2") (pinfunction "I1_2") (pintype "input"))
    )
    (net (code "92") (name "unconnected-(IC2A-O-Pad3)") (class "Default")
      (node (ref "IC2") (pin "3") (pinfunction "O_3") (pintype "output"))
    )
    (net (code "93") (name "unconnected-(IC2B-I0-Pad5)") (class "Default")
      (node (ref "IC2") (pin "5") (pinfunction "I0_5") (pintype "input"))
    )
    (net (code "94") (name "unconnected-(IC2B-I1-Pad6)") (class "Default")
      (node (ref "IC2") (pin "6") (pinfunction "I1_6") (pintype "input"))
    )
    (net (code "95") (name "unconnected-(IC2B-O-Pad4)") (class "Default")
      (node (ref "IC2") (pin "4") (pinfunction "O_4") (pintype "output"))
    )
    (net (code "96") (name "unconnected-(IC2C-I0-Pad8)") (class "Default")
      (node (ref "IC2") (pin "8") (pinfunction "I0_8") (pintype "input"))
    )
    (net (code "97") (name "unconnected-(IC2C-I1-Pad9)") (class "Default")
      (node (ref "IC2") (pin "9") (pinfunction "I1_9") (pintype "input"))
    )
    (net (code "98") (name "unconnected-(IC2C-O-Pad10)") (class "Default")
      (node (ref "IC2") (pin "10") (pinfunction "O_10") (pintype "output"))
    )
    (net (code "99") (name "unconnected-(IC2D-I0-Pad12)") (class "Default")
      (node (ref "IC2") (pin "12") (pinfunction "I0_12") (pintype "input"))
    )
    (net (code "100") (name "unconnected-(IC2D-I1-Pad13)") (class "Default")
      (node (ref "IC2") (pin "13") (pinfunction "I1_13") (pintype "input"))
    )
    (net (code "101") (name "unconnected-(IC2D-O-Pad11)") (class "Default")
      (node (ref "IC2") (pin "11") (pinfunction "O_11") (pintype "output"))
    )
    (net (code "102") (name "unconnected-(U$11-NC-Pad13)") (class "Default")
      (node (ref "U$11") (pin "13") (pinfunction "NC_13") (pintype "no_connect"))
    )
    (net (code "103") (name "unconnected-(U1-AIO1-Pad35)") (class "Default")
      (node (ref "U1") (pin "35") (pinfunction "AIO1_35") (pintype "bidirectional"))
    )
    (net (code "104") (name "unconnected-(U1-AIO2-Pad30)") (class "Default")
      (node (ref "U1") (pin "30") (pinfunction "AIO2_30") (pintype "bidirectional"))
    )
    (net (code "105") (name "unconnected-(U1-NC-Pad26)") (class "Default")
      (node (ref "U1") (pin "26") (pinfunction "NC_26") (pintype "bidirectional"))
    )
    (net (code "106") (name "unconnected-(U1-PCMCLK-Pad7)") (class "Default")
      (node (ref "U1") (pin "7") (pinfunction "PCMCLK_7") (pintype "bidirectional"))
    )
    (net (code "107") (name "unconnected-(U1-PCMIN-Pad9)") (class "Default")
      (node (ref "U1") (pin "9") (pinfunction "PCMIN_9") (pintype "bidirectional"))
    )
    (net (code "108") (name "unconnected-(U1-PCMOUT-Pad10)") (class "Default")
      (node (ref "U1") (pin "10") (pinfunction "PCMOUT_10") (pintype "bidirectional"))
    )
    (net (code "109") (name "unconnected-(U1-PCMSYNC-Pad8)") (class "Default")
      (node (ref "U1") (pin "8") (pinfunction "PCMSYNC_8") (pintype "bidirectional"))
    )
    (net (code "110") (name "unconnected-(U1-PIO3-Pad20)") (class "Default")
      (node (ref "U1") (pin "20") (pinfunction "PIO3_20") (pintype "bidirectional"))
    )
    (net (code "111") (name "unconnected-(U1-PIO6-Pad3)") (class "Default")
      (node (ref "U1") (pin "3") (pinfunction "PIO6_3") (pintype "bidirectional"))
    )
    (net (code "112") (name "unconnected-(U1-PIO7-Pad4)") (class "Default")
      (node (ref "U1") (pin "4") (pinfunction "PIO7_4") (pintype "bidirectional"))
    )
    (net (code "113") (name "unconnected-(U1-PIO8-Pad31)") (class "Default")
      (node (ref "U1") (pin "31") (pinfunction "PIO8_31") (pintype "bidirectional"))
    )
    (net (code "114") (name "unconnected-(U1-PIO9-Pad32)") (class "Default")
      (node (ref "U1") (pin "32") (pinfunction "PIO9_32") (pintype "bidirectional"))
    )
    (net (code "115") (name "unconnected-(U1-PIO10-Pad33)") (class "Default")
      (node (ref "U1") (pin "33") (pinfunction "PIO10_33") (pintype "bidirectional"))
    )
    (net (code "116") (name "unconnected-(U1-PIO11-Pad34)") (class "Default")
      (node (ref "U1") (pin "34") (pinfunction "PIO11_34") (pintype "bidirectional"))
    )
    (net (code "117") (name "unconnected-(U1-RESET-Pad5)") (class "Default")
      (node (ref "U1") (pin "5") (pinfunction "RESET_5") (pintype "bidirectional"))
    )
    (net (code "118") (name "unconnected-(U1-SPICLK-Pad6)") (class "Default")
      (node (ref "U1") (pin "6") (pinfunction "SPICLK_6") (pintype "bidirectional"))
    )
    (net (code "119") (name "unconnected-(U1-SPICSB-Pad23)") (class "Default")
      (node (ref "U1") (pin "23") (pinfunction "SPICSB_23") (pintype "bidirectional"))
    )
    (net (code "120") (name "unconnected-(U1-SPIMISO-Pad24)") (class "Default")
      (node (ref "U1") (pin "24") (pinfunction "SPIMISO_24") (pintype "bidirectional"))
    )
    (net (code "121") (name "unconnected-(U1-SPIMOSI-Pad2)") (class "Default")
      (node (ref "U1") (pin "2") (pinfunction "SPIMOSI_2") (pintype "bidirectional"))
    )
    (net (code "122") (name "unconnected-(U1-USBD+-Pad17)") (class "Default")
      (node (ref "U1") (pin "17") (pinfunction "USBD+_17") (pintype "bidirectional"))
    )
    (net (code "123") (name "unconnected-(U1-USBD--Pad18)") (class "Default")
      (node (ref "U1") (pin "18") (pinfunction "USBD-_18") (pintype "bidirectional"))
    )
    (net (code "124") (name "unconnected-(U5-NC-PadP$3)") (class "Default")
      (node (ref "U5") (pin "P$3") (pinfunction "NC_P$3") (pintype "bidirectional"))
    )
    (net (code "125") (name "unconnected-(U5-RESERVED_1-PadP$2)") (class "Default")
      (node (ref "U5") (pin "P$2") (pinfunction "RESERVED_1_P$2") (pintype "bidirectional"))
    )
    (net (code "126") (name "unconnected-(U5-RESERVED_2-PadP$4)") (class "Default")
      (node (ref "U5") (pin "P$4") (pinfunction "RESERVED_2_P$4") (pintype "bidirectional"))
    )
    (net (code "127") (name "unconnected-(U5-RESERVED_3-PadP$24)") (class "Default")
      (node (ref "U5") (pin "P$24") (pinfunction "RESERVED_3_P$24") (pintype "bidirectional"))
    )
  )
)
